# picoKey_230404.net
KiCad netlist of a schematic drawn in EAGLE
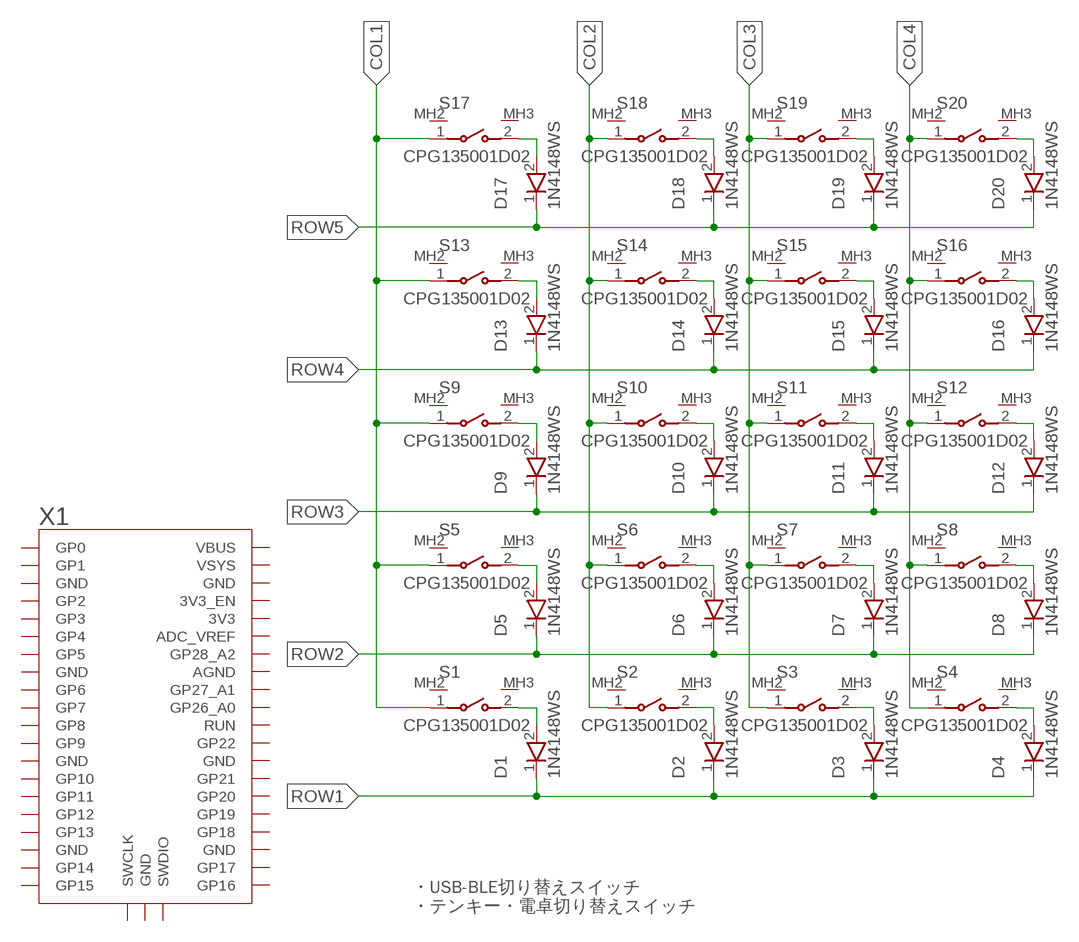
[diagram p0: schematic, sheet 1]

(export (version "E")
  (design (tool "Eeschema 10.0.6"))
  (components
    (comp (ref "D1")
      (value "1N4148WS")
      (footprint "eagle-import:SODFL2512X90N")
      (fields (field (name "MOUSER_PART_NUMBER") "512-1N4148WS"))
      (libsource (lib "eagle-import") (part "1N4148WS"))
    )
    (comp (ref "D2")
      (value "1N4148WS")
      (footprint "eagle-import:SODFL2512X90N")
      (fields (field (name "MOUSER_PART_NUMBER") "512-1N4148WS"))
      (libsource (lib "eagle-import") (part "1N4148WS"))
    )
    (comp (ref "D3")
      (value "1N4148WS")
      (footprint "eagle-import:SODFL2512X90N")
      (fields (field (name "MOUSER_PART_NUMBER") "512-1N4148WS"))
      (libsource (lib "eagle-import") (part "1N4148WS"))
    )
    (comp (ref "D4")
      (value "1N4148WS")
      (footprint "eagle-import:SODFL2512X90N")
      (fields (field (name "MOUSER_PART_NUMBER") "512-1N4148WS"))
      (libsource (lib "eagle-import") (part "1N4148WS"))
    )
    (comp (ref "D5")
      (value "1N4148WS")
      (footprint "eagle-import:SODFL2512X90N")
      (fields (field (name "MOUSER_PART_NUMBER") "512-1N4148WS"))
      (libsource (lib "eagle-import") (part "1N4148WS"))
    )
    (comp (ref "D6")
      (value "1N4148WS")
      (footprint "eagle-import:SODFL2512X90N")
      (fields (field (name "MOUSER_PART_NUMBER") "512-1N4148WS"))
      (libsource (lib "eagle-import") (part "1N4148WS"))
    )
    (comp (ref "D7")
      (value "1N4148WS")
      (footprint "eagle-import:SODFL2512X90N")
      (fields (field (name "MOUSER_PART_NUMBER") "512-1N4148WS"))
      (libsource (lib "eagle-import") (part "1N4148WS"))
    )
    (comp (ref "D8")
      (value "1N4148WS")
      (footprint "eagle-import:SODFL2512X90N")
      (fields (field (name "MOUSER_PART_NUMBER") "512-1N4148WS"))
      (libsource (lib "eagle-import") (part "1N4148WS"))
    )
    (comp (ref "D9")
      (value "1N4148WS")
      (footprint "eagle-import:SODFL2512X90N")
      (fields (field (name "MOUSER_PART_NUMBER") "512-1N4148WS"))
      (libsource (lib "eagle-import") (part "1N4148WS"))
    )
    (comp (ref "D10")
      (value "1N4148WS")
      (footprint "eagle-import:SODFL2512X90N")
      (fields (field (name "MOUSER_PART_NUMBER") "512-1N4148WS"))
      (libsource (lib "eagle-import") (part "1N4148WS"))
    )
    (comp (ref "D11")
      (value "1N4148WS")
      (footprint "eagle-import:SODFL2512X90N")
      (fields (field (name "MOUSER_PART_NUMBER") "512-1N4148WS"))
      (libsource (lib "eagle-import") (part "1N4148WS"))
    )
    (comp (ref "D12")
      (value "1N4148WS")
      (footprint "eagle-import:SODFL2512X90N")
      (fields (field (name "MOUSER_PART_NUMBER") "512-1N4148WS"))
      (libsource (lib "eagle-import") (part "1N4148WS"))
    )
    (comp (ref "D13")
      (value "1N4148WS")
      (footprint "eagle-import:SODFL2512X90N")
      (fields (field (name "MOUSER_PART_NUMBER") "512-1N4148WS"))
      (libsource (lib "eagle-import") (part "1N4148WS"))
    )
    (comp (ref "D14")
      (value "1N4148WS")
      (footprint "eagle-import:SODFL2512X90N")
      (fields (field (name "MOUSER_PART_NUMBER") "512-1N4148WS"))
      (libsource (lib "eagle-import") (part "1N4148WS"))
    )
    (comp (ref "D15")
      (value "1N4148WS")
      (footprint "eagle-import:SODFL2512X90N")
      (fields (field (name "MOUSER_PART_NUMBER") "512-1N4148WS"))
      (libsource (lib "eagle-import") (part "1N4148WS"))
    )
    (comp (ref "D16")
      (value "1N4148WS")
      (footprint "eagle-import:SODFL2512X90N")
      (fields (field (name "MOUSER_PART_NUMBER") "512-1N4148WS"))
      (libsource (lib "eagle-import") (part "1N4148WS"))
    )
    (comp (ref "D17")
      (value "1N4148WS")
      (footprint "eagle-import:SODFL2512X90N")
      (fields (field (name "MOUSER_PART_NUMBER") "512-1N4148WS"))
      (libsource (lib "eagle-import") (part "1N4148WS"))
    )
    (comp (ref "D18")
      (value "1N4148WS")
      (footprint "eagle-import:SODFL2512X90N")
      (fields (field (name "MOUSER_PART_NUMBER") "512-1N4148WS"))
      (libsource (lib "eagle-import") (part "1N4148WS"))
    )
    (comp (ref "D19")
      (value "1N4148WS")
      (footprint "eagle-import:SODFL2512X90N")
      (fields (field (name "MOUSER_PART_NUMBER") "512-1N4148WS"))
      (libsource (lib "eagle-import") (part "1N4148WS"))
    )
    (comp (ref "D20")
      (value "1N4148WS")
      (footprint "eagle-import:SODFL2512X90N")
      (fields (field (name "MOUSER_PART_NUMBER") "512-1N4148WS"))
      (libsource (lib "eagle-import") (part "1N4148WS"))
    )
    (comp (ref "S1")
      (value "CPG135001D02")
      (footprint "eagle-import:CPG135001D02")
      (libsource (lib "eagle-import") (part "CPG135001D02"))
    )
    (comp (ref "S2")
      (value "CPG135001D02")
      (footprint "eagle-import:CPG135001D02")
      (libsource (lib "eagle-import") (part "CPG135001D02"))
    )
    (comp (ref "S3")
      (value "CPG135001D02")
      (footprint "eagle-import:CPG135001D02")
      (libsource (lib "eagle-import") (part "CPG135001D02"))
    )
    (comp (ref "S4")
      (value "CPG135001D02")
      (footprint "eagle-import:CPG135001D02")
      (libsource (lib "eagle-import") (part "CPG135001D02"))
    )
    (comp (ref "S5")
      (value "CPG135001D02")
      (footprint "eagle-import:CPG135001D02")
      (libsource (lib "eagle-import") (part "CPG135001D02"))
    )
    (comp (ref "S6")
      (value "CPG135001D02")
      (footprint "eagle-import:CPG135001D02")
      (libsource (lib "eagle-import") (part "CPG135001D02"))
    )
    (comp (ref "S7")
      (value "CPG135001D02")
      (footprint "eagle-import:CPG135001D02")
      (libsource (lib "eagle-import") (part "CPG135001D02"))
    )
    (comp (ref "S8")
      (value "CPG135001D02")
      (footprint "eagle-import:CPG135001D02")
      (libsource (lib "eagle-import") (part "CPG135001D02"))
    )
    (comp (ref "S9")
      (value "CPG135001D02")
      (footprint "eagle-import:CPG135001D02")
      (libsource (lib "eagle-import") (part "CPG135001D02"))
    )
    (comp (ref "S10")
      (value "CPG135001D02")
      (footprint "eagle-import:CPG135001D02")
      (libsource (lib "eagle-import") (part "CPG135001D02"))
    )
    (comp (ref "S11")
      (value "CPG135001D02")
      (footprint "eagle-import:CPG135001D02")
      (libsource (lib "eagle-import") (part "CPG135001D02"))
    )
    (comp (ref "S12")
      (value "CPG135001D02")
      (footprint "eagle-import:CPG135001D02")
      (libsource (lib "eagle-import") (part "CPG135001D02"))
    )
    (comp (ref "S13")
      (value "CPG135001D02")
      (footprint "eagle-import:CPG135001D02")
      (libsource (lib "eagle-import") (part "CPG135001D02"))
    )
    (comp (ref "S14")
      (value "CPG135001D02")
      (footprint "eagle-import:CPG135001D02")
      (libsource (lib "eagle-import") (part "CPG135001D02"))
    )
    (comp (ref "S15")
      (value "CPG135001D02")
      (footprint "eagle-import:CPG135001D02")
      (libsource (lib "eagle-import") (part "CPG135001D02"))
    )
    (comp (ref "S16")
      (value "CPG135001D02")
      (footprint "eagle-import:CPG135001D02")
      (libsource (lib "eagle-import") (part "CPG135001D02"))
    )
    (comp (ref "S17")
      (value "CPG135001D02")
      (footprint "eagle-import:CPG135001D02")
      (libsource (lib "eagle-import") (part "CPG135001D02"))
    )
    (comp (ref "S18")
      (value "CPG135001D02")
      (footprint "eagle-import:CPG135001D02")
      (libsource (lib "eagle-import") (part "CPG135001D02"))
    )
    (comp (ref "S19")
      (value "CPG135001D02")
      (footprint "eagle-import:CPG135001D02")
      (libsource (lib "eagle-import") (part "CPG135001D02"))
    )
    (comp (ref "S20")
      (value "CPG135001D02")
      (footprint "eagle-import:CPG135001D02")
      (libsource (lib "eagle-import") (part "CPG135001D02"))
    )
    (comp (ref "X1")
      (value "RASPBERRYPI_PICO_RPI_PICO_IG-TH")
      (footprint "eagle-import:RASPBERRYPI_PICO_RPI_PICO_TH")
      (libsource (lib "eagle-import") (part "RASPBERRYPI_PICO_RPI_PICO_IG-TH"))
    )
  )
  (nets
    (net (code "1") (name "COL1") (class "Default")
      (node (ref "S1") (pin "1") (pinfunction "1_1") (pintype "bidirectional"))
      (node (ref "S13") (pin "1") (pinfunction "1_1") (pintype "bidirectional"))
      (node (ref "S17") (pin "1") (pinfunction "1_1") (pintype "bidirectional"))
      (node (ref "S5") (pin "1") (pinfunction "1_1") (pintype "bidirectional"))
      (node (ref "S9") (pin "1") (pinfunction "1_1") (pintype "bidirectional"))
    )
    (net (code "2") (name "COL2") (class "Default")
      (node (ref "S10") (pin "1") (pinfunction "1_1") (pintype "bidirectional"))
      (node (ref "S14") (pin "1") (pinfunction "1_1") (pintype "bidirectional"))
      (node (ref "S18") (pin "1") (pinfunction "1_1") (pintype "bidirectional"))
      (node (ref "S2") (pin "1") (pinfunction "1_1") (pintype "bidirectional"))
      (node (ref "S6") (pin "1") (pinfunction "1_1") (pintype "bidirectional"))
    )
    (net (code "3") (name "COL3") (class "Default")
      (node (ref "S11") (pin "1") (pinfunction "1_1") (pintype "bidirectional"))
      (node (ref "S15") (pin "1") (pinfunction "1_1") (pintype "bidirectional"))
      (node (ref "S19") (pin "1") (pinfunction "1_1") (pintype "bidirectional"))
      (node (ref "S3") (pin "1") (pinfunction "1_1") (pintype "bidirectional"))
      (node (ref "S7") (pin "1") (pinfunction "1_1") (pintype "bidirectional"))
    )
    (net (code "4") (name "COL4") (class "Default")
      (node (ref "S12") (pin "1") (pinfunction "1_1") (pintype "bidirectional"))
      (node (ref "S16") (pin "1") (pinfunction "1_1") (pintype "bidirectional"))
      (node (ref "S20") (pin "1") (pinfunction "1_1") (pintype "bidirectional"))
      (node (ref "S4") (pin "1") (pinfunction "1_1") (pintype "bidirectional"))
      (node (ref "S8") (pin "1") (pinfunction "1_1") (pintype "bidirectional"))
    )
    (net (code "5") (name "Net-(D1-A)") (class "Default")
      (node (ref "D1") (pin "2") (pinfunction "A_2") (pintype "bidirectional"))
      (node (ref "S1") (pin "2") (pinfunction "2_2") (pintype "bidirectional"))
    )
    (net (code "6") (name "Net-(D2-A)") (class "Default")
      (node (ref "D2") (pin "2") (pinfunction "A_2") (pintype "bidirectional"))
      (node (ref "S2") (pin "2") (pinfunction "2_2") (pintype "bidirectional"))
    )
    (net (code "7") (name "Net-(D3-A)") (class "Default")
      (node (ref "D3") (pin "2") (pinfunction "A_2") (pintype "bidirectional"))
      (node (ref "S3") (pin "2") (pinfunction "2_2") (pintype "bidirectional"))
    )
    (net (code "8") (name "Net-(D4-A)") (class "Default")
      (node (ref "D4") (pin "2") (pinfunction "A_2") (pintype "bidirectional"))
      (node (ref "S4") (pin "2") (pinfunction "2_2") (pintype "bidirectional"))
    )
    (net (code "9") (name "Net-(D5-A)") (class "Default")
      (node (ref "D5") (pin "2") (pinfunction "A_2") (pintype "bidirectional"))
      (node (ref "S5") (pin "2") (pinfunction "2_2") (pintype "bidirectional"))
    )
    (net (code "10") (name "Net-(D6-A)") (class "Default")
      (node (ref "D6") (pin "2") (pinfunction "A_2") (pintype "bidirectional"))
      (node (ref "S6") (pin "2") (pinfunction "2_2") (pintype "bidirectional"))
    )
    (net (code "11") (name "Net-(D7-A)") (class "Default")
      (node (ref "D7") (pin "2") (pinfunction "A_2") (pintype "bidirectional"))
      (node (ref "S7") (pin "2") (pinfunction "2_2") (pintype "bidirectional"))
    )
    (net (code "12") (name "Net-(D8-A)") (class "Default")
      (node (ref "D8") (pin "2") (pinfunction "A_2") (pintype "bidirectional"))
      (node (ref "S8") (pin "2") (pinfunction "2_2") (pintype "bidirectional"))
    )
    (net (code "13") (name "Net-(D9-A)") (class "Default")
      (node (ref "D9") (pin "2") (pinfunction "A_2") (pintype "bidirectional"))
      (node (ref "S9") (pin "2") (pinfunction "2_2") (pintype "bidirectional"))
    )
    (net (code "14") (name "Net-(D10-A)") (class "Default")
      (node (ref "D10") (pin "2") (pinfunction "A_2") (pintype "bidirectional"))
      (node (ref "S10") (pin "2") (pinfunction "2_2") (pintype "bidirectional"))
    )
    (net (code "15") (name "Net-(D11-A)") (class "Default")
      (node (ref "D11") (pin "2") (pinfunction "A_2") (pintype "bidirectional"))
      (node (ref "S11") (pin "2") (pinfunction "2_2") (pintype "bidirectional"))
    )
    (net (code "16") (name "Net-(D12-A)") (class "Default")
      (node (ref "D12") (pin "2") (pinfunction "A_2") (pintype "bidirectional"))
      (node (ref "S12") (pin "2") (pinfunction "2_2") (pintype "bidirectional"))
    )
    (net (code "17") (name "Net-(D13-A)") (class "Default")
      (node (ref "D13") (pin "2") (pinfunction "A_2") (pintype "bidirectional"))
      (node (ref "S13") (pin "2") (pinfunction "2_2") (pintype "bidirectional"))
    )
    (net (code "18") (name "Net-(D14-A)") (class "Default")
      (node (ref "D14") (pin "2") (pinfunction "A_2") (pintype "bidirectional"))
      (node (ref "S14") (pin "2") (pinfunction "2_2") (pintype "bidirectional"))
    )
    (net (code "19") (name "Net-(D15-A)") (class "Default")
      (node (ref "D15") (pin "2") (pinfunction "A_2") (pintype "bidirectional"))
      (node (ref "S15") (pin "2") (pinfunction "2_2") (pintype "bidirectional"))
    )
    (net (code "20") (name "Net-(D16-A)") (class "Default")
      (node (ref "D16") (pin "2") (pinfunction "A_2") (pintype "bidirectional"))
      (node (ref "S16") (pin "2") (pinfunction "2_2") (pintype "bidirectional"))
    )
    (net (code "21") (name "Net-(D17-A)") (class "Default")
      (node (ref "D17") (pin "2") (pinfunction "A_2") (pintype "bidirectional"))
      (node (ref "S17") (pin "2") (pinfunction "2_2") (pintype "bidirectional"))
    )
    (net (code "22") (name "Net-(D18-A)") (class "Default")
      (node (ref "D18") (pin "2") (pinfunction "A_2") (pintype "bidirectional"))
      (node (ref "S18") (pin "2") (pinfunction "2_2") (pintype "bidirectional"))
    )
    (net (code "23") (name "Net-(D19-A)") (class "Default")
      (node (ref "D19") (pin "2") (pinfunction "A_2") (pintype "bidirectional"))
      (node (ref "S19") (pin "2") (pinfunction "2_2") (pintype "bidirectional"))
    )
    (net (code "24") (name "Net-(D20-A)") (class "Default")
      (node (ref "D20") (pin "2") (pinfunction "A_2") (pintype "bidirectional"))
      (node (ref "S20") (pin "2") (pinfunction "2_2") (pintype "bidirectional"))
    )
    (net (code "25") (name "ROW1") (class "Default")
      (node (ref "D1") (pin "1") (pinfunction "K_1") (pintype "bidirectional"))
      (node (ref "D2") (pin "1") (pinfunction "K_1") (pintype "bidirectional"))
      (node (ref "D3") (pin "1") (pinfunction "K_1") (pintype "bidirectional"))
      (node (ref "D4") (pin "1") (pinfunction "K_1") (pintype "bidirectional"))
    )
    (net (code "26") (name "ROW2") (class "Default")
      (node (ref "D5") (pin "1") (pinfunction "K_1") (pintype "bidirectional"))
      (node (ref "D6") (pin "1") (pinfunction "K_1") (pintype "bidirectional"))
      (node (ref "D7") (pin "1") (pinfunction "K_1") (pintype "bidirectional"))
      (node (ref "D8") (pin "1") (pinfunction "K_1") (pintype "bidirectional"))
    )
    (net (code "27") (name "ROW3") (class "Default")
      (node (ref "D10") (pin "1") (pinfunction "K_1") (pintype "bidirectional"))
      (node (ref "D11") (pin "1") (pinfunction "K_1") (pintype "bidirectional"))
      (node (ref "D12") (pin "1") (pinfunction "K_1") (pintype "bidirectional"))
      (node (ref "D9") (pin "1") (pinfunction "K_1") (pintype "bidirectional"))
    )
    (net (code "28") (name "ROW4") (class "Default")
      (node (ref "D13") (pin "1") (pinfunction "K_1") (pintype "bidirectional"))
      (node (ref "D14") (pin "1") (pinfunction "K_1") (pintype "bidirectional"))
      (node (ref "D15") (pin "1") (pinfunction "K_1") (pintype "bidirectional"))
      (node (ref "D16") (pin "1") (pinfunction "K_1") (pintype "bidirectional"))
    )
    (net (code "29") (name "ROW5") (class "Default")
      (node (ref "D17") (pin "1") (pinfunction "K_1") (pintype "bidirectional"))
      (node (ref "D18") (pin "1") (pinfunction "K_1") (pintype "bidirectional"))
      (node (ref "D19") (pin "1") (pinfunction "K_1") (pintype "bidirectional"))
      (node (ref "D20") (pin "1") (pinfunction "K_1") (pintype "bidirectional"))
    )
    (net (code "30") (name "unconnected-(S1-MH-PadMH2)") (class "Default")
      (node (ref "S1") (pin "MH2") (pinfunction "MH_MH2") (pintype "bidirectional"))
    )
    (net (code "31") (name "unconnected-(S1-MH-PadMH3)") (class "Default")
      (node (ref "S1") (pin "MH3") (pinfunction "MH_MH3") (pintype "bidirectional"))
    )
    (net (code "32") (name "unconnected-(S2-MH-PadMH2)") (class "Default")
      (node (ref "S2") (pin "MH2") (pinfunction "MH_MH2") (pintype "bidirectional"))
    )
    (net (code "33") (name "unconnected-(S2-MH-PadMH3)") (class "Default")
      (node (ref "S2") (pin "MH3") (pinfunction "MH_MH3") (pintype "bidirectional"))
    )
    (net (code "34") (name "unconnected-(S3-MH-PadMH2)") (class "Default")
      (node (ref "S3") (pin "MH2") (pinfunction "MH_MH2") (pintype "bidirectional"))
    )
    (net (code "35") (name "unconnected-(S3-MH-PadMH3)") (class "Default")
      (node (ref "S3") (pin "MH3") (pinfunction "MH_MH3") (pintype "bidirectional"))
    )
    (net (code "36") (name "unconnected-(S4-MH-PadMH2)") (class "Default")
      (node (ref "S4") (pin "MH2") (pinfunction "MH_MH2") (pintype "bidirectional"))
    )
    (net (code "37") (name "unconnected-(S4-MH-PadMH3)") (class "Default")
      (node (ref "S4") (pin "MH3") (pinfunction "MH_MH3") (pintype "bidirectional"))
    )
    (net (code "38") (name "unconnected-(S5-MH-PadMH2)") (class "Default")
      (node (ref "S5") (pin "MH2") (pinfunction "MH_MH2") (pintype "bidirectional"))
    )
    (net (code "39") (name "unconnected-(S5-MH-PadMH3)") (class "Default")
      (node (ref "S5") (pin "MH3") (pinfunction "MH_MH3") (pintype "bidirectional"))
    )
    (net (code "40") (name "unconnected-(S6-MH-PadMH2)") (class "Default")
      (node (ref "S6") (pin "MH2") (pinfunction "MH_MH2") (pintype "bidirectional"))
    )
    (net (code "41") (name "unconnected-(S6-MH-PadMH3)") (class "Default")
      (node (ref "S6") (pin "MH3") (pinfunction "MH_MH3") (pintype "bidirectional"))
    )
    (net (code "42") (name "unconnected-(S7-MH-PadMH2)") (class "Default")
      (node (ref "S7") (pin "MH2") (pinfunction "MH_MH2") (pintype "bidirectional"))
    )
    (net (code "43") (name "unconnected-(S7-MH-PadMH3)") (class "Default")
      (node (ref "S7") (pin "MH3") (pinfunction "MH_MH3") (pintype "bidirectional"))
    )
    (net (code "44") (name "unconnected-(S8-MH-PadMH2)") (class "Default")
      (node (ref "S8") (pin "MH2") (pinfunction "MH_MH2") (pintype "bidirectional"))
    )
    (net (code "45") (name "unconnected-(S8-MH-PadMH3)") (class "Default")
      (node (ref "S8") (pin "MH3") (pinfunction "MH_MH3") (pintype "bidirectional"))
    )
    (net (code "46") (name "unconnected-(S9-MH-PadMH2)") (class "Default")
      (node (ref "S9") (pin "MH2") (pinfunction "MH_MH2") (pintype "bidirectional"))
    )
    (net (code "47") (name "unconnected-(S9-MH-PadMH3)") (class "Default")
      (node (ref "S9") (pin "MH3") (pinfunction "MH_MH3") (pintype "bidirectional"))
    )
    (net (code "48") (name "unconnected-(S10-MH-PadMH2)") (class "Default")
      (node (ref "S10") (pin "MH2") (pinfunction "MH_MH2") (pintype "bidirectional"))
    )
    (net (code "49") (name "unconnected-(S10-MH-PadMH3)") (class "Default")
      (node (ref "S10") (pin "MH3") (pinfunction "MH_MH3") (pintype "bidirectional"))
    )
    (net (code "50") (name "unconnected-(S11-MH-PadMH2)") (class "Default")
      (node (ref "S11") (pin "MH2") (pinfunction "MH_MH2") (pintype "bidirectional"))
    )
    (net (code "51") (name "unconnected-(S11-MH-PadMH3)") (class "Default")
      (node (ref "S11") (pin "MH3") (pinfunction "MH_MH3") (pintype "bidirectional"))
    )
    (net (code "52") (name "unconnected-(S12-MH-PadMH2)") (class "Default")
      (node (ref "S12") (pin "MH2") (pinfunction "MH_MH2") (pintype "bidirectional"))
    )
    (net (code "53") (name "unconnected-(S12-MH-PadMH3)") (class "Default")
      (node (ref "S12") (pin "MH3") (pinfunction "MH_MH3") (pintype "bidirectional"))
    )
    (net (code "54") (name "unconnected-(S13-MH-PadMH2)") (class "Default")
      (node (ref "S13") (pin "MH2") (pinfunction "MH_MH2") (pintype "bidirectional"))
    )
    (net (code "55") (name "unconnected-(S13-MH-PadMH3)") (class "Default")
      (node (ref "S13") (pin "MH3") (pinfunction "MH_MH3") (pintype "bidirectional"))
    )
    (net (code "56") (name "unconnected-(S14-MH-PadMH2)") (class "Default")
      (node (ref "S14") (pin "MH2") (pinfunction "MH_MH2") (pintype "bidirectional"))
    )
    (net (code "57") (name "unconnected-(S14-MH-PadMH3)") (class "Default")
      (node (ref "S14") (pin "MH3") (pinfunction "MH_MH3") (pintype "bidirectional"))
    )
    (net (code "58") (name "unconnected-(S15-MH-PadMH2)") (class "Default")
      (node (ref "S15") (pin "MH2") (pinfunction "MH_MH2") (pintype "bidirectional"))
    )
    (net (code "59") (name "unconnected-(S15-MH-PadMH3)") (class "Default")
      (node (ref "S15") (pin "MH3") (pinfunction "MH_MH3") (pintype "bidirectional"))
    )
    (net (code "60") (name "unconnected-(S16-MH-PadMH2)") (class "Default")
      (node (ref "S16") (pin "MH2") (pinfunction "MH_MH2") (pintype "bidirectional"))
    )
    (net (code "61") (name "unconnected-(S16-MH-PadMH3)") (class "Default")
      (node (ref "S16") (pin "MH3") (pinfunction "MH_MH3") (pintype "bidirectional"))
    )
    (net (code "62") (name "unconnected-(S17-MH-PadMH2)") (class "Default")
      (node (ref "S17") (pin "MH2") (pinfunction "MH_MH2") (pintype "bidirectional"))
    )
    (net (code "63") (name "unconnected-(S17-MH-PadMH3)") (class "Default")
      (node (ref "S17") (pin "MH3") (pinfunction "MH_MH3") (pintype "bidirectional"))
    )
    (net (code "64") (name "unconnected-(S18-MH-PadMH2)") (class "Default")
      (node (ref "S18") (pin "MH2") (pinfunction "MH_MH2") (pintype "bidirectional"))
    )
    (net (code "65") (name "unconnected-(S18-MH-PadMH3)") (class "Default")
      (node (ref "S18") (pin "MH3") (pinfunction "MH_MH3") (pintype "bidirectional"))
    )
    (net (code "66") (name "unconnected-(S19-MH-PadMH2)") (class "Default")
      (node (ref "S19") (pin "MH2") (pinfunction "MH_MH2") (pintype "bidirectional"))
    )
    (net (code "67") (name "unconnected-(S19-MH-PadMH3)") (class "Default")
      (node (ref "S19") (pin "MH3") (pinfunction "MH_MH3") (pintype "bidirectional"))
    )
    (net (code "68") (name "unconnected-(S20-MH-PadMH2)") (class "Default")
      (node (ref "S20") (pin "MH2") (pinfunction "MH_MH2") (pintype "bidirectional"))
    )
    (net (code "69") (name "unconnected-(S20-MH-PadMH3)") (class "Default")
      (node (ref "S20") (pin "MH3") (pinfunction "MH_MH3") (pintype "bidirectional"))
    )
    (net (code "70") (name "unconnected-(X1-GND-PadGND@1)") (class "Default")
      (node (ref "X1") (pin "GND@1") (pinfunction "GND_GND@1") (pintype "bidirectional"))
    )
    (net (code "71") (name "unconnected-(X1-GND-PadGND@2)") (class "Default")
      (node (ref "X1") (pin "GND@2") (pinfunction "GND_GND@2") (pintype "bidirectional"))
    )
    (net (code "72") (name "unconnected-(X1-GND-PadGND@3)") (class "Default")
      (node (ref "X1") (pin "GND@3") (pinfunction "GND_GND@3") (pintype "bidirectional"))
    )
    (net (code "73") (name "unconnected-(X1-GND-PadGND@4)") (class "Default")
      (node (ref "X1") (pin "GND@4") (pinfunction "GND_GND@4") (pintype "bidirectional"))
    )
    (net (code "74") (name "unconnected-(X1-GND-PadGND@5)") (class "Default")
      (node (ref "X1") (pin "GND@5") (pinfunction "GND_GND@5") (pintype "bidirectional"))
    )
    (net (code "75") (name "unconnected-(X1-GND-PadGND@6)") (class "Default")
      (node (ref "X1") (pin "GND@6") (pinfunction "GND_GND@6") (pintype "bidirectional"))
    )
    (net (code "76") (name "unconnected-(X1-GND-PadGND@7)") (class "Default")
      (node (ref "X1") (pin "GND@7") (pinfunction "GND_GND@7") (pintype "bidirectional"))
    )
    (net (code "77") (name "unconnected-(X1-GND-PadGND@8)") (class "Default")
      (node (ref "X1") (pin "GND@8") (pinfunction "GND_GND@8") (pintype "bidirectional"))
    )
    (net (code "78") (name "unconnected-(X1-Pad3V3)") (class "Default")
      (node (ref "X1") (pin "3V3") (pinfunction "3V3_3V3") (pintype "bidirectional"))
    )
    (net (code "79") (name "unconnected-(X1-Pad3V3_EN)") (class "Default")
      (node (ref "X1") (pin "3V3_EN") (pinfunction "3V3_EN_3V3_EN") (pintype "bidirectional"))
    )
    (net (code "80") (name "unconnected-(X1-PadADC_VREF)") (class "Default")
      (node (ref "X1") (pin "ADC_VREF") (pinfunction "ADC_VREF_ADC_VREF") (pintype "bidirectional"))
    )
    (net (code "81") (name "unconnected-(X1-PadAGND)") (class "Default")
      (node (ref "X1") (pin "AGND") (pinfunction "AGND_AGND") (pintype "bidirectional"))
    )
    (net (code "82") (name "unconnected-(X1-PadGP0)") (class "Default")
      (node (ref "X1") (pin "GP0") (pinfunction "GP0_GP0") (pintype "bidirectional"))
    )
    (net (code "83") (name "unconnected-(X1-PadGP1)") (class "Default")
      (node (ref "X1") (pin "GP1") (pinfunction "GP1_GP1") (pintype "bidirectional"))
    )
    (net (code "84") (name "unconnected-(X1-PadGP2)") (class "Default")
      (node (ref "X1") (pin "GP2") (pinfunction "GP2_GP2") (pintype "bidirectional"))
    )
    (net (code "85") (name "unconnected-(X1-PadGP3)") (class "Default")
      (node (ref "X1") (pin "GP3") (pinfunction "GP3_GP3") (pintype "bidirectional"))
    )
    (net (code "86") (name "unconnected-(X1-PadGP4)") (class "Default")
      (node (ref "X1") (pin "GP4") (pinfunction "GP4_GP4") (pintype "bidirectional"))
    )
    (net (code "87") (name "unconnected-(X1-PadGP5)") (class "Default")
      (node (ref "X1") (pin "GP5") (pinfunction "GP5_GP5") (pintype "bidirectional"))
    )
    (net (code "88") (name "unconnected-(X1-PadGP6)") (class "Default")
      (node (ref "X1") (pin "GP6") (pinfunction "GP6_GP6") (pintype "bidirectional"))
    )
    (net (code "89") (name "unconnected-(X1-PadGP7)") (class "Default")
      (node (ref "X1") (pin "GP7") (pinfunction "GP7_GP7") (pintype "bidirectional"))
    )
    (net (code "90") (name "unconnected-(X1-PadGP8)") (class "Default")
      (node (ref "X1") (pin "GP8") (pinfunction "GP8_GP8") (pintype "bidirectional"))
    )
    (net (code "91") (name "unconnected-(X1-PadGP9)") (class "Default")
      (node (ref "X1") (pin "GP9") (pinfunction "GP9_GP9") (pintype "bidirectional"))
    )
    (net (code "92") (name "unconnected-(X1-PadGP10)") (class "Default")
      (node (ref "X1") (pin "GP10") (pinfunction "GP10_GP10") (pintype "bidirectional"))
    )
    (net (code "93") (name "unconnected-(X1-PadGP11)") (class "Default")
      (node (ref "X1") (pin "GP11") (pinfunction "GP11_GP11") (pintype "bidirectional"))
    )
    (net (code "94") (name "unconnected-(X1-PadGP12)") (class "Default")
      (node (ref "X1") (pin "GP12") (pinfunction "GP12_GP12") (pintype "bidirectional"))
    )
    (net (code "95") (name "unconnected-(X1-PadGP13)") (class "Default")
      (node (ref "X1") (pin "GP13") (pinfunction "GP13_GP13") (pintype "bidirectional"))
    )
    (net (code "96") (name "unconnected-(X1-PadGP14)") (class "Default")
      (node (ref "X1") (pin "GP14") (pinfunction "GP14_GP14") (pintype "bidirectional"))
    )
    (net (code "97") (name "unconnected-(X1-PadGP15)") (class "Default")
      (node (ref "X1") (pin "GP15") (pinfunction "GP15_GP15") (pintype "bidirectional"))
    )
    (net (code "98") (name "unconnected-(X1-PadGP16)") (class "Default")
      (node (ref "X1") (pin "GP16") (pinfunction "GP16_GP16") (pintype "bidirectional"))
    )
    (net (code "99") (name "unconnected-(X1-PadGP17)") (class "Default")
      (node (ref "X1") (pin "GP17") (pinfunction "GP17_GP17") (pintype "bidirectional"))
    )
    (net (code "100") (name "unconnected-(X1-PadGP18)") (class "Default")
      (node (ref "X1") (pin "GP18") (pinfunction "GP18_GP18") (pintype "bidirectional"))
    )
    (net (code "101") (name "unconnected-(X1-PadGP19)") (class "Default")
      (node (ref "X1") (pin "GP19") (pinfunction "GP19_GP19") (pintype "bidirectional"))
    )
    (net (code "102") (name "unconnected-(X1-PadGP20)") (class "Default")
      (node (ref "X1") (pin "GP20") (pinfunction "GP20_GP20") (pintype "bidirectional"))
    )
    (net (code "103") (name "unconnected-(X1-PadGP21)") (class "Default")
      (node (ref "X1") (pin "GP21") (pinfunction "GP21_GP21") (pintype "bidirectional"))
    )
    (net (code "104") (name "unconnected-(X1-PadGP22)") (class "Default")
      (node (ref "X1") (pin "GP22") (pinfunction "GP22_GP22") (pintype "bidirectional"))
    )
    (net (code "105") (name "unconnected-(X1-PadGP26_A0)") (class "Default")
      (node (ref "X1") (pin "GP26_A0") (pinfunction "GP26_A0_GP26_A0") (pintype "bidirectional"))
    )
    (net (code "106") (name "unconnected-(X1-PadGP27_A1)") (class "Default")
      (node (ref "X1") (pin "GP27_A1") (pinfunction "GP27_A1_GP27_A1") (pintype "bidirectional"))
    )
    (net (code "107") (name "unconnected-(X1-PadGP28_A2)") (class "Default")
      (node (ref "X1") (pin "GP28_A2") (pinfunction "GP28_A2_GP28_A2") (pintype "bidirectional"))
    )
    (net (code "108") (name "unconnected-(X1-PadRUN)") (class "Default")
      (node (ref "X1") (pin "RUN") (pinfunction "RUN_RUN") (pintype "bidirectional"))
    )
    (net (code "109") (name "unconnected-(X1-PadSWCLK)") (class "Default")
      (node (ref "X1") (pin "SWCLK") (pinfunction "SWCLK_SWCLK") (pintype "bidirectional"))
    )
    (net (code "110") (name "unconnected-(X1-PadSWDIO)") (class "Default")
      (node (ref "X1") (pin "SWDIO") (pinfunction "SWDIO_SWDIO") (pintype "bidirectional"))
    )
    (net (code "111") (name "unconnected-(X1-PadVBUS)") (class "Default")
      (node (ref "X1") (pin "VBUS") (pinfunction "VBUS_VBUS") (pintype "bidirectional"))
    )
    (net (code "112") (name "unconnected-(X1-PadVSYS)") (class "Default")
      (node (ref "X1") (pin "VSYS") (pinfunction "VSYS_VSYS") (pintype "bidirectional"))
    )
  )
)
